# Rectifier_mk2.net
KiCad netlist of a schematic drawn in EAGLE
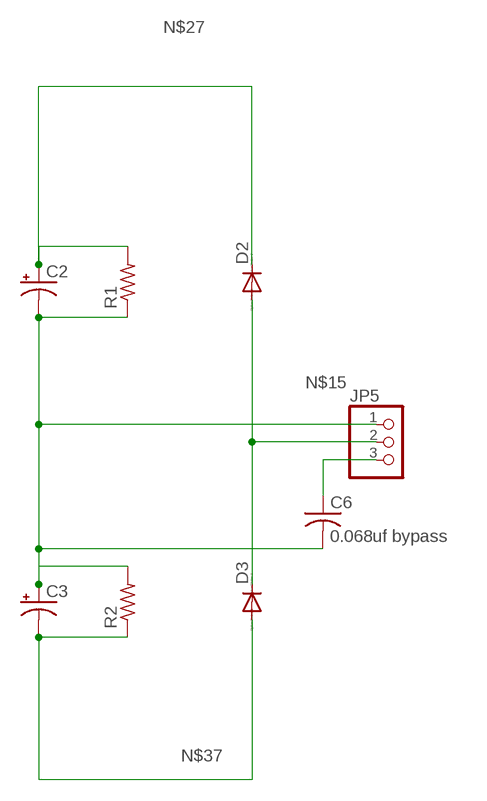
[diagram p0: schematic, sheet 1]

(export (version "E")
  (design (tool "Eeschema 10.0.6"))
  (components
    (comp (ref "C2")
      (value "CPOL-USE10-35")
      (footprint "eagle-import:EB35D")
      (libsource (lib "eagle-import") (part "CPOL-USE10-35"))
    )
    (comp (ref "C3")
      (value "CPOL-USE10-35")
      (footprint "eagle-import:EB35D")
      (libsource (lib "eagle-import") (part "CPOL-USE10-35"))
    )
    (comp (ref "C6")
      (value "0.068uf bypass")
      (footprint "eagle-import:C150-084X183")
      (libsource (lib "eagle-import") (part "C-US150-084X183"))
    )
    (comp (ref "D2")
      (value "DIODE-TO220V")
      (footprint "eagle-import:TO220ACS")
      (libsource (lib "eagle-import") (part "DIODE-TO220V"))
    )
    (comp (ref "D3")
      (value "DIODE-TO220V")
      (footprint "eagle-import:TO220ACS")
      (libsource (lib "eagle-import") (part "DIODE-TO220V"))
    )
    (comp (ref "JP5")
      (value "PINHD-1X3-9.5")
      (footprint "eagle-import:1X03-9.5")
      (libsource (lib "eagle-import") (part "PINHD-1X3-9.5"))
    )
    (comp (ref "R1")
      (value "R-US_0207/10")
      (footprint "eagle-import:0207_10")
      (libsource (lib "eagle-import") (part "R-US_0207/10"))
    )
    (comp (ref "R2")
      (value "R-US_0207/10")
      (footprint "eagle-import:0207_10")
      (libsource (lib "eagle-import") (part "R-US_0207/10"))
    )
  )
  (nets
    (net (code "1") (name "/N$15") (class "Default")
      (node (ref "D2") (pin "A") (pinfunction "A_A") (pintype "passive"))
      (node (ref "D3") (pin "C") (pinfunction "C_C") (pintype "passive"))
      (node (ref "JP5") (pin "2") (pinfunction "2_2") (pintype "passive"))
    )
    (net (code "2") (name "/N$27") (class "Default")
      (node (ref "C2") (pin "+") (pinfunction "+_+") (pintype "passive"))
      (node (ref "D2") (pin "C") (pinfunction "C_C") (pintype "passive"))
      (node (ref "R1") (pin "2") (pinfunction "2_2") (pintype "passive"))
    )
    (net (code "3") (name "/N$37") (class "Default")
      (node (ref "C3") (pin "-") (pinfunction "-_-") (pintype "passive"))
      (node (ref "D3") (pin "A") (pinfunction "A_A") (pintype "passive"))
      (node (ref "R2") (pin "1") (pinfunction "1_1") (pintype "passive"))
    )
    (net (code "4") (name "Net-(C2-Pad-)") (class "Default")
      (node (ref "C2") (pin "-") (pinfunction "-_-") (pintype "passive"))
      (node (ref "C3") (pin "+") (pinfunction "+_+") (pintype "passive"))
      (node (ref "C6") (pin "2") (pinfunction "2_2") (pintype "passive"))
      (node (ref "JP5") (pin "1") (pinfunction "1_1") (pintype "passive"))
      (node (ref "R1") (pin "1") (pinfunction "1_1") (pintype "passive"))
      (node (ref "R2") (pin "2") (pinfunction "2_2") (pintype "passive"))
    )
    (net (code "5") (name "Net-(C6-Pad1)") (class "Default")
      (node (ref "C6") (pin "1") (pinfunction "1_1") (pintype "passive"))
      (node (ref "JP5") (pin "3") (pinfunction "3_3") (pintype "passive"))
    )
  )
)
